# dac-eval-psu.net
KiCad netlist of a schematic drawn in EAGLE
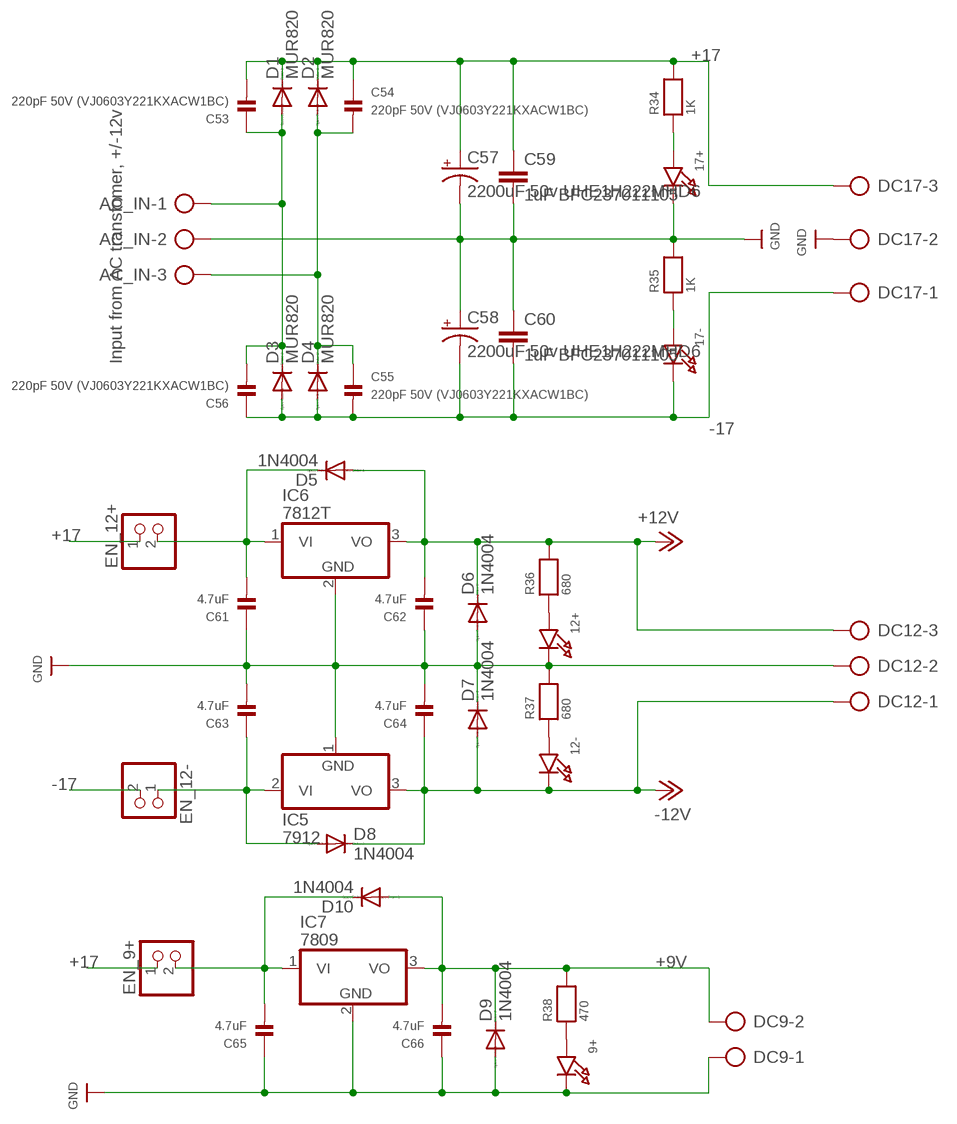
[diagram p0: schematic, sheet 1]

(export (version "E")
  (design (tool "Eeschema 10.0.6"))
  (components
    (comp (ref "9+")
      (value "LED0603")
      (footprint "eagle-import:CHIPLED_0603")
      (libsource (lib "eagle-import") (part "LED0603"))
    )
    (comp (ref "12+")
      (value "LED0603")
      (footprint "eagle-import:CHIPLED_0603")
      (libsource (lib "eagle-import") (part "LED0603"))
    )
    (comp (ref "12-")
      (value "LED0603")
      (footprint "eagle-import:CHIPLED_0603")
      (libsource (lib "eagle-import") (part "LED0603"))
    )
    (comp (ref "17+")
      (value "LED0603")
      (footprint "eagle-import:CHIPLED_0603")
      (libsource (lib "eagle-import") (part "LED0603"))
    )
    (comp (ref "17-")
      (value "LED0603")
      (footprint "eagle-import:CHIPLED_0603")
      (libsource (lib "eagle-import") (part "LED0603"))
    )
    (comp (ref "AC_IN")
      (value "AK500/3")
      (footprint "eagle-import:AK500_3")
      (libsource (lib "eagle-import") (part "AK500/3"))
    )
    (comp (ref "C53")
      (value "220pF 50V (VJ0603Y221KXACW1BC)")
      (footprint "eagle-import:0603")
      (libsource (lib "eagle-import") (part "CAP_CERAMIC0603"))
    )
    (comp (ref "C54")
      (value "220pF 50V (VJ0603Y221KXACW1BC)")
      (footprint "eagle-import:0603")
      (libsource (lib "eagle-import") (part "CAP_CERAMIC0603"))
    )
    (comp (ref "C55")
      (value "220pF 50V (VJ0603Y221KXACW1BC)")
      (footprint "eagle-import:0603")
      (libsource (lib "eagle-import") (part "CAP_CERAMIC0603"))
    )
    (comp (ref "C56")
      (value "220pF 50V (VJ0603Y221KXACW1BC)")
      (footprint "eagle-import:0603")
      (libsource (lib "eagle-import") (part "CAP_CERAMIC0603"))
    )
    (comp (ref "C57")
      (value "2200uF 50v UHE1H222MHD6")
      (footprint "eagle-import:E7,5-18")
      (libsource (lib "eagle-import") (part "CPOL-USE7.5-18"))
    )
    (comp (ref "C58")
      (value "2200uF 50v UHE1H222MHD6")
      (footprint "eagle-import:E7,5-18")
      (libsource (lib "eagle-import") (part "CPOL-USE7.5-18"))
    )
    (comp (ref "C59")
      (value "1uF BFC237011105")
      (footprint "eagle-import:C5B7.2")
      (libsource (lib "eagle-import") (part "C5/7.2"))
    )
    (comp (ref "C60")
      (value "1uF BFC237011105")
      (footprint "eagle-import:C5B7.2")
      (libsource (lib "eagle-import") (part "C5/7.2"))
    )
    (comp (ref "C61")
      (value "4.7uF")
      (footprint "eagle-import:0603")
      (libsource (lib "eagle-import") (part "CAP_CERAMIC0603"))
    )
    (comp (ref "C62")
      (value "4.7uF")
      (footprint "eagle-import:0603")
      (libsource (lib "eagle-import") (part "CAP_CERAMIC0603"))
    )
    (comp (ref "C63")
      (value "4.7uF")
      (footprint "eagle-import:0603")
      (libsource (lib "eagle-import") (part "CAP_CERAMIC0603"))
    )
    (comp (ref "C64")
      (value "4.7uF")
      (footprint "eagle-import:0603")
      (libsource (lib "eagle-import") (part "CAP_CERAMIC0603"))
    )
    (comp (ref "C65")
      (value "4.7uF")
      (footprint "eagle-import:0603")
      (libsource (lib "eagle-import") (part "CAP_CERAMIC0603"))
    )
    (comp (ref "C66")
      (value "4.7uF")
      (footprint "eagle-import:0603")
      (libsource (lib "eagle-import") (part "CAP_CERAMIC0603"))
    )
    (comp (ref "D1")
      (value "MUR820")
      (footprint "eagle-import:C221B1A")
      (libsource (lib "eagle-import") (part "MUR820"))
    )
    (comp (ref "D2")
      (value "MUR820")
      (footprint "eagle-import:C221B1A")
      (libsource (lib "eagle-import") (part "MUR820"))
    )
    (comp (ref "D3")
      (value "MUR820")
      (footprint "eagle-import:C221B1A")
      (libsource (lib "eagle-import") (part "MUR820"))
    )
    (comp (ref "D4")
      (value "MUR820")
      (footprint "eagle-import:C221B1A")
      (libsource (lib "eagle-import") (part "MUR820"))
    )
    (comp (ref "D5")
      (value "1N4004")
      (footprint "eagle-import:DO41-10")
      (libsource (lib "eagle-import") (part "1N4004"))
    )
    (comp (ref "D6")
      (value "1N4004")
      (footprint "eagle-import:DO41-10")
      (libsource (lib "eagle-import") (part "1N4004"))
    )
    (comp (ref "D7")
      (value "1N4004")
      (footprint "eagle-import:DO41-10")
      (libsource (lib "eagle-import") (part "1N4004"))
    )
    (comp (ref "D8")
      (value "1N4004")
      (footprint "eagle-import:DO41-10")
      (libsource (lib "eagle-import") (part "1N4004"))
    )
    (comp (ref "D9")
      (value "1N4004")
      (footprint "eagle-import:DO41-10")
      (libsource (lib "eagle-import") (part "1N4004"))
    )
    (comp (ref "D10")
      (value "1N4004")
      (footprint "eagle-import:DO41-10")
      (libsource (lib "eagle-import") (part "1N4004"))
    )
    (comp (ref "DC9")
      (value "AK500/2")
      (footprint "eagle-import:AK500_2")
      (libsource (lib "eagle-import") (part "AK500/2"))
    )
    (comp (ref "DC12")
      (value "AK500/3")
      (footprint "eagle-import:AK500_3")
      (libsource (lib "eagle-import") (part "AK500/3"))
    )
    (comp (ref "DC17")
      (value "AK500/3")
      (footprint "eagle-import:AK500_3")
      (libsource (lib "eagle-import") (part "AK500/3"))
    )
    (comp (ref "EN_9+")
      (value "HEADER-1X2ROUND")
      (footprint "eagle-import:1X02_ROUND")
      (libsource (lib "eagle-import") (part "HEADER-1X2ROUND"))
    )
    (comp (ref "EN_12+")
      (value "HEADER-1X2ROUND")
      (footprint "eagle-import:1X02_ROUND")
      (libsource (lib "eagle-import") (part "HEADER-1X2ROUND"))
    )
    (comp (ref "EN_12-")
      (value "HEADER-1X2ROUND")
      (footprint "eagle-import:1X02_ROUND")
      (libsource (lib "eagle-import") (part "HEADER-1X2ROUND"))
    )
    (comp (ref "IC5")
      (value "7912")
      (footprint "eagle-import:TO220H")
      (libsource (lib "eagle-import") (part "79T12"))
    )
    (comp (ref "IC6")
      (value "7812T")
      (footprint "eagle-import:TO220H")
      (libsource (lib "eagle-import") (part "78T12"))
    )
    (comp (ref "IC7")
      (value "7809")
      (footprint "eagle-import:TO220H")
      (libsource (lib "eagle-import") (part "78T12"))
    )
    (comp (ref "R34")
      (value "1K")
      (footprint "eagle-import:0603")
      (libsource (lib "eagle-import") (part "RESISTOR0603"))
    )
    (comp (ref "R35")
      (value "1K")
      (footprint "eagle-import:0603")
      (libsource (lib "eagle-import") (part "RESISTOR0603"))
    )
    (comp (ref "R36")
      (value "680")
      (footprint "eagle-import:0603")
      (libsource (lib "eagle-import") (part "RESISTOR0603"))
    )
    (comp (ref "R37")
      (value "680")
      (footprint "eagle-import:0603")
      (libsource (lib "eagle-import") (part "RESISTOR0603"))
    )
    (comp (ref "R38")
      (value "470")
      (footprint "eagle-import:0603")
      (libsource (lib "eagle-import") (part "RESISTOR0603"))
    )
  )
  (nets
    (net (code "1") (name "+12V") (class "Default")
      (node (ref "C62") (pin "2") (pinfunction "P$2_2") (pintype "passive"))
      (node (ref "D5") (pin "A") (pinfunction "A_A") (pintype "passive"))
      (node (ref "D6") (pin "C") (pinfunction "C_C") (pintype "passive"))
      (node (ref "DC12") (pin "3") (pinfunction "KL_3") (pintype "passive"))
      (node (ref "IC6") (pin "3") (pinfunction "VO_3") (pintype "passive"))
      (node (ref "R36") (pin "2") (pinfunction "2_2") (pintype "passive"))
    )
    (net (code "2") (name "-12V") (class "Default")
      (node (ref "12-") (pin "C") (pinfunction "C_C") (pintype "passive"))
      (node (ref "C64") (pin "1") (pinfunction "P$1_1") (pintype "passive"))
      (node (ref "D7") (pin "A") (pinfunction "A_A") (pintype "passive"))
      (node (ref "D8") (pin "C") (pinfunction "C_C") (pintype "passive"))
      (node (ref "DC12") (pin "1") (pinfunction "KL_1") (pintype "passive"))
      (node (ref "IC5") (pin "3") (pinfunction "VO_3") (pintype "passive"))
    )
    (net (code "3") (name "/+9V") (class "Default")
      (node (ref "C66") (pin "2") (pinfunction "P$2_2") (pintype "passive"))
      (node (ref "D10") (pin "A") (pinfunction "A_A") (pintype "passive"))
      (node (ref "D9") (pin "C") (pinfunction "C_C") (pintype "passive"))
      (node (ref "DC9") (pin "2") (pinfunction "KL_2") (pintype "passive"))
      (node (ref "IC7") (pin "3") (pinfunction "VO_3") (pintype "passive"))
      (node (ref "R38") (pin "2") (pinfunction "2_2") (pintype "passive"))
    )
    (net (code "4") (name "/+17") (class "Default")
      (node (ref "C53") (pin "2") (pinfunction "P$2_2") (pintype "passive"))
      (node (ref "C54") (pin "1") (pinfunction "P$1_1") (pintype "passive"))
      (node (ref "C57") (pin "+") (pinfunction "+_+") (pintype "passive"))
      (node (ref "C59") (pin "1") (pinfunction "1_1") (pintype "passive"))
      (node (ref "D1") (pin "C") (pinfunction "C_C") (pintype "passive"))
      (node (ref "D2") (pin "C") (pinfunction "C_C") (pintype "passive"))
      (node (ref "DC17") (pin "3") (pinfunction "KL_3") (pintype "passive"))
      (node (ref "EN_12+") (pin "1") (pinfunction "1_1") (pintype "passive"))
      (node (ref "EN_9+") (pin "1") (pinfunction "1_1") (pintype "passive"))
      (node (ref "R34") (pin "2") (pinfunction "2_2") (pintype "passive"))
    )
    (net (code "5") (name "/-17") (class "Default")
      (node (ref "17-") (pin "C") (pinfunction "C_C") (pintype "passive"))
      (node (ref "C55") (pin "2") (pinfunction "P$2_2") (pintype "passive"))
      (node (ref "C56") (pin "1") (pinfunction "P$1_1") (pintype "passive"))
      (node (ref "C58") (pin "-") (pinfunction "-_-") (pintype "passive"))
      (node (ref "C60") (pin "2") (pinfunction "2_2") (pintype "passive"))
      (node (ref "D3") (pin "A") (pinfunction "A_A") (pintype "passive"))
      (node (ref "D4") (pin "A") (pinfunction "A_A") (pintype "passive"))
      (node (ref "DC17") (pin "1") (pinfunction "KL_1") (pintype "passive"))
      (node (ref "EN_12-") (pin "2") (pinfunction "2_2") (pintype "passive"))
    )
    (net (code "6") (name "GND") (class "Default")
      (node (ref "12+") (pin "C") (pinfunction "C_C") (pintype "passive"))
      (node (ref "17+") (pin "C") (pinfunction "C_C") (pintype "passive"))
      (node (ref "9+") (pin "C") (pinfunction "C_C") (pintype "passive"))
      (node (ref "AC_IN") (pin "2") (pinfunction "KL_2") (pintype "passive"))
      (node (ref "C57") (pin "-") (pinfunction "-_-") (pintype "passive"))
      (node (ref "C58") (pin "+") (pinfunction "+_+") (pintype "passive"))
      (node (ref "C59") (pin "2") (pinfunction "2_2") (pintype "passive"))
      (node (ref "C60") (pin "1") (pinfunction "1_1") (pintype "passive"))
      (node (ref "C61") (pin "1") (pinfunction "P$1_1") (pintype "passive"))
      (node (ref "C62") (pin "1") (pinfunction "P$1_1") (pintype "passive"))
      (node (ref "C63") (pin "2") (pinfunction "P$2_2") (pintype "passive"))
      (node (ref "C64") (pin "2") (pinfunction "P$2_2") (pintype "passive"))
      (node (ref "C65") (pin "1") (pinfunction "P$1_1") (pintype "passive"))
      (node (ref "C66") (pin "1") (pinfunction "P$1_1") (pintype "passive"))
      (node (ref "D6") (pin "A") (pinfunction "A_A") (pintype "passive"))
      (node (ref "D7") (pin "C") (pinfunction "C_C") (pintype "passive"))
      (node (ref "D9") (pin "A") (pinfunction "A_A") (pintype "passive"))
      (node (ref "DC12") (pin "2") (pinfunction "KL_2") (pintype "passive"))
      (node (ref "DC17") (pin "2") (pinfunction "KL_2") (pintype "passive"))
      (node (ref "DC9") (pin "1") (pinfunction "KL_1") (pintype "passive"))
      (node (ref "IC5") (pin "1") (pinfunction "GND_1") (pintype "passive"))
      (node (ref "IC6") (pin "2") (pinfunction "GND_2") (pintype "passive"))
      (node (ref "IC7") (pin "2") (pinfunction "GND_2") (pintype "passive"))
      (node (ref "R35") (pin "2") (pinfunction "2_2") (pintype "passive"))
      (node (ref "R37") (pin "2") (pinfunction "2_2") (pintype "passive"))
    )
    (net (code "7") (name "Net-(9+-PadA)") (class "Default")
      (node (ref "9+") (pin "A") (pinfunction "A_A") (pintype "passive"))
      (node (ref "R38") (pin "1") (pinfunction "1_1") (pintype "passive"))
    )
    (net (code "8") (name "Net-(12+-PadA)") (class "Default")
      (node (ref "12+") (pin "A") (pinfunction "A_A") (pintype "passive"))
      (node (ref "R36") (pin "1") (pinfunction "1_1") (pintype "passive"))
    )
    (net (code "9") (name "Net-(12--PadA)") (class "Default")
      (node (ref "12-") (pin "A") (pinfunction "A_A") (pintype "passive"))
      (node (ref "R37") (pin "1") (pinfunction "1_1") (pintype "passive"))
    )
    (net (code "10") (name "Net-(17+-PadA)") (class "Default")
      (node (ref "17+") (pin "A") (pinfunction "A_A") (pintype "passive"))
      (node (ref "R34") (pin "1") (pinfunction "1_1") (pintype "passive"))
    )
    (net (code "11") (name "Net-(17--PadA)") (class "Default")
      (node (ref "17-") (pin "A") (pinfunction "A_A") (pintype "passive"))
      (node (ref "R35") (pin "1") (pinfunction "1_1") (pintype "passive"))
    )
    (net (code "12") (name "Net-(AC_INA-KL)") (class "Default")
      (node (ref "AC_IN") (pin "1") (pinfunction "KL_1") (pintype "passive"))
      (node (ref "C53") (pin "1") (pinfunction "P$1_1") (pintype "passive"))
      (node (ref "C56") (pin "2") (pinfunction "P$2_2") (pintype "passive"))
      (node (ref "D1") (pin "A") (pinfunction "A_A") (pintype "passive"))
      (node (ref "D3") (pin "C") (pinfunction "C_C") (pintype "passive"))
    )
    (net (code "13") (name "Net-(AC_INC-KL)") (class "Default")
      (node (ref "AC_IN") (pin "3") (pinfunction "KL_3") (pintype "passive"))
      (node (ref "C54") (pin "2") (pinfunction "P$2_2") (pintype "passive"))
      (node (ref "C55") (pin "1") (pinfunction "P$1_1") (pintype "passive"))
      (node (ref "D2") (pin "A") (pinfunction "A_A") (pintype "passive"))
      (node (ref "D4") (pin "C") (pinfunction "C_C") (pintype "passive"))
    )
    (net (code "14") (name "Net-(C61-P$2)") (class "Default")
      (node (ref "C61") (pin "2") (pinfunction "P$2_2") (pintype "passive"))
      (node (ref "D5") (pin "C") (pinfunction "C_C") (pintype "passive"))
      (node (ref "EN_12+") (pin "2") (pinfunction "2_2") (pintype "passive"))
      (node (ref "IC6") (pin "1") (pinfunction "VI_1") (pintype "input"))
    )
    (net (code "15") (name "Net-(C63-P$1)") (class "Default")
      (node (ref "C63") (pin "1") (pinfunction "P$1_1") (pintype "passive"))
      (node (ref "D8") (pin "A") (pinfunction "A_A") (pintype "passive"))
      (node (ref "EN_12-") (pin "1") (pinfunction "1_1") (pintype "passive"))
      (node (ref "IC5") (pin "2") (pinfunction "VI_2") (pintype "input"))
    )
    (net (code "16") (name "Net-(C65-P$2)") (class "Default")
      (node (ref "C65") (pin "2") (pinfunction "P$2_2") (pintype "passive"))
      (node (ref "D10") (pin "C") (pinfunction "C_C") (pintype "passive"))
      (node (ref "EN_9+") (pin "2") (pinfunction "2_2") (pintype "passive"))
      (node (ref "IC7") (pin "1") (pinfunction "VI_1") (pintype "input"))
    )
  )
)
